# PROC051D_RST_LEDs.net
KiCad netlist of a schematic drawn in Altium Designer
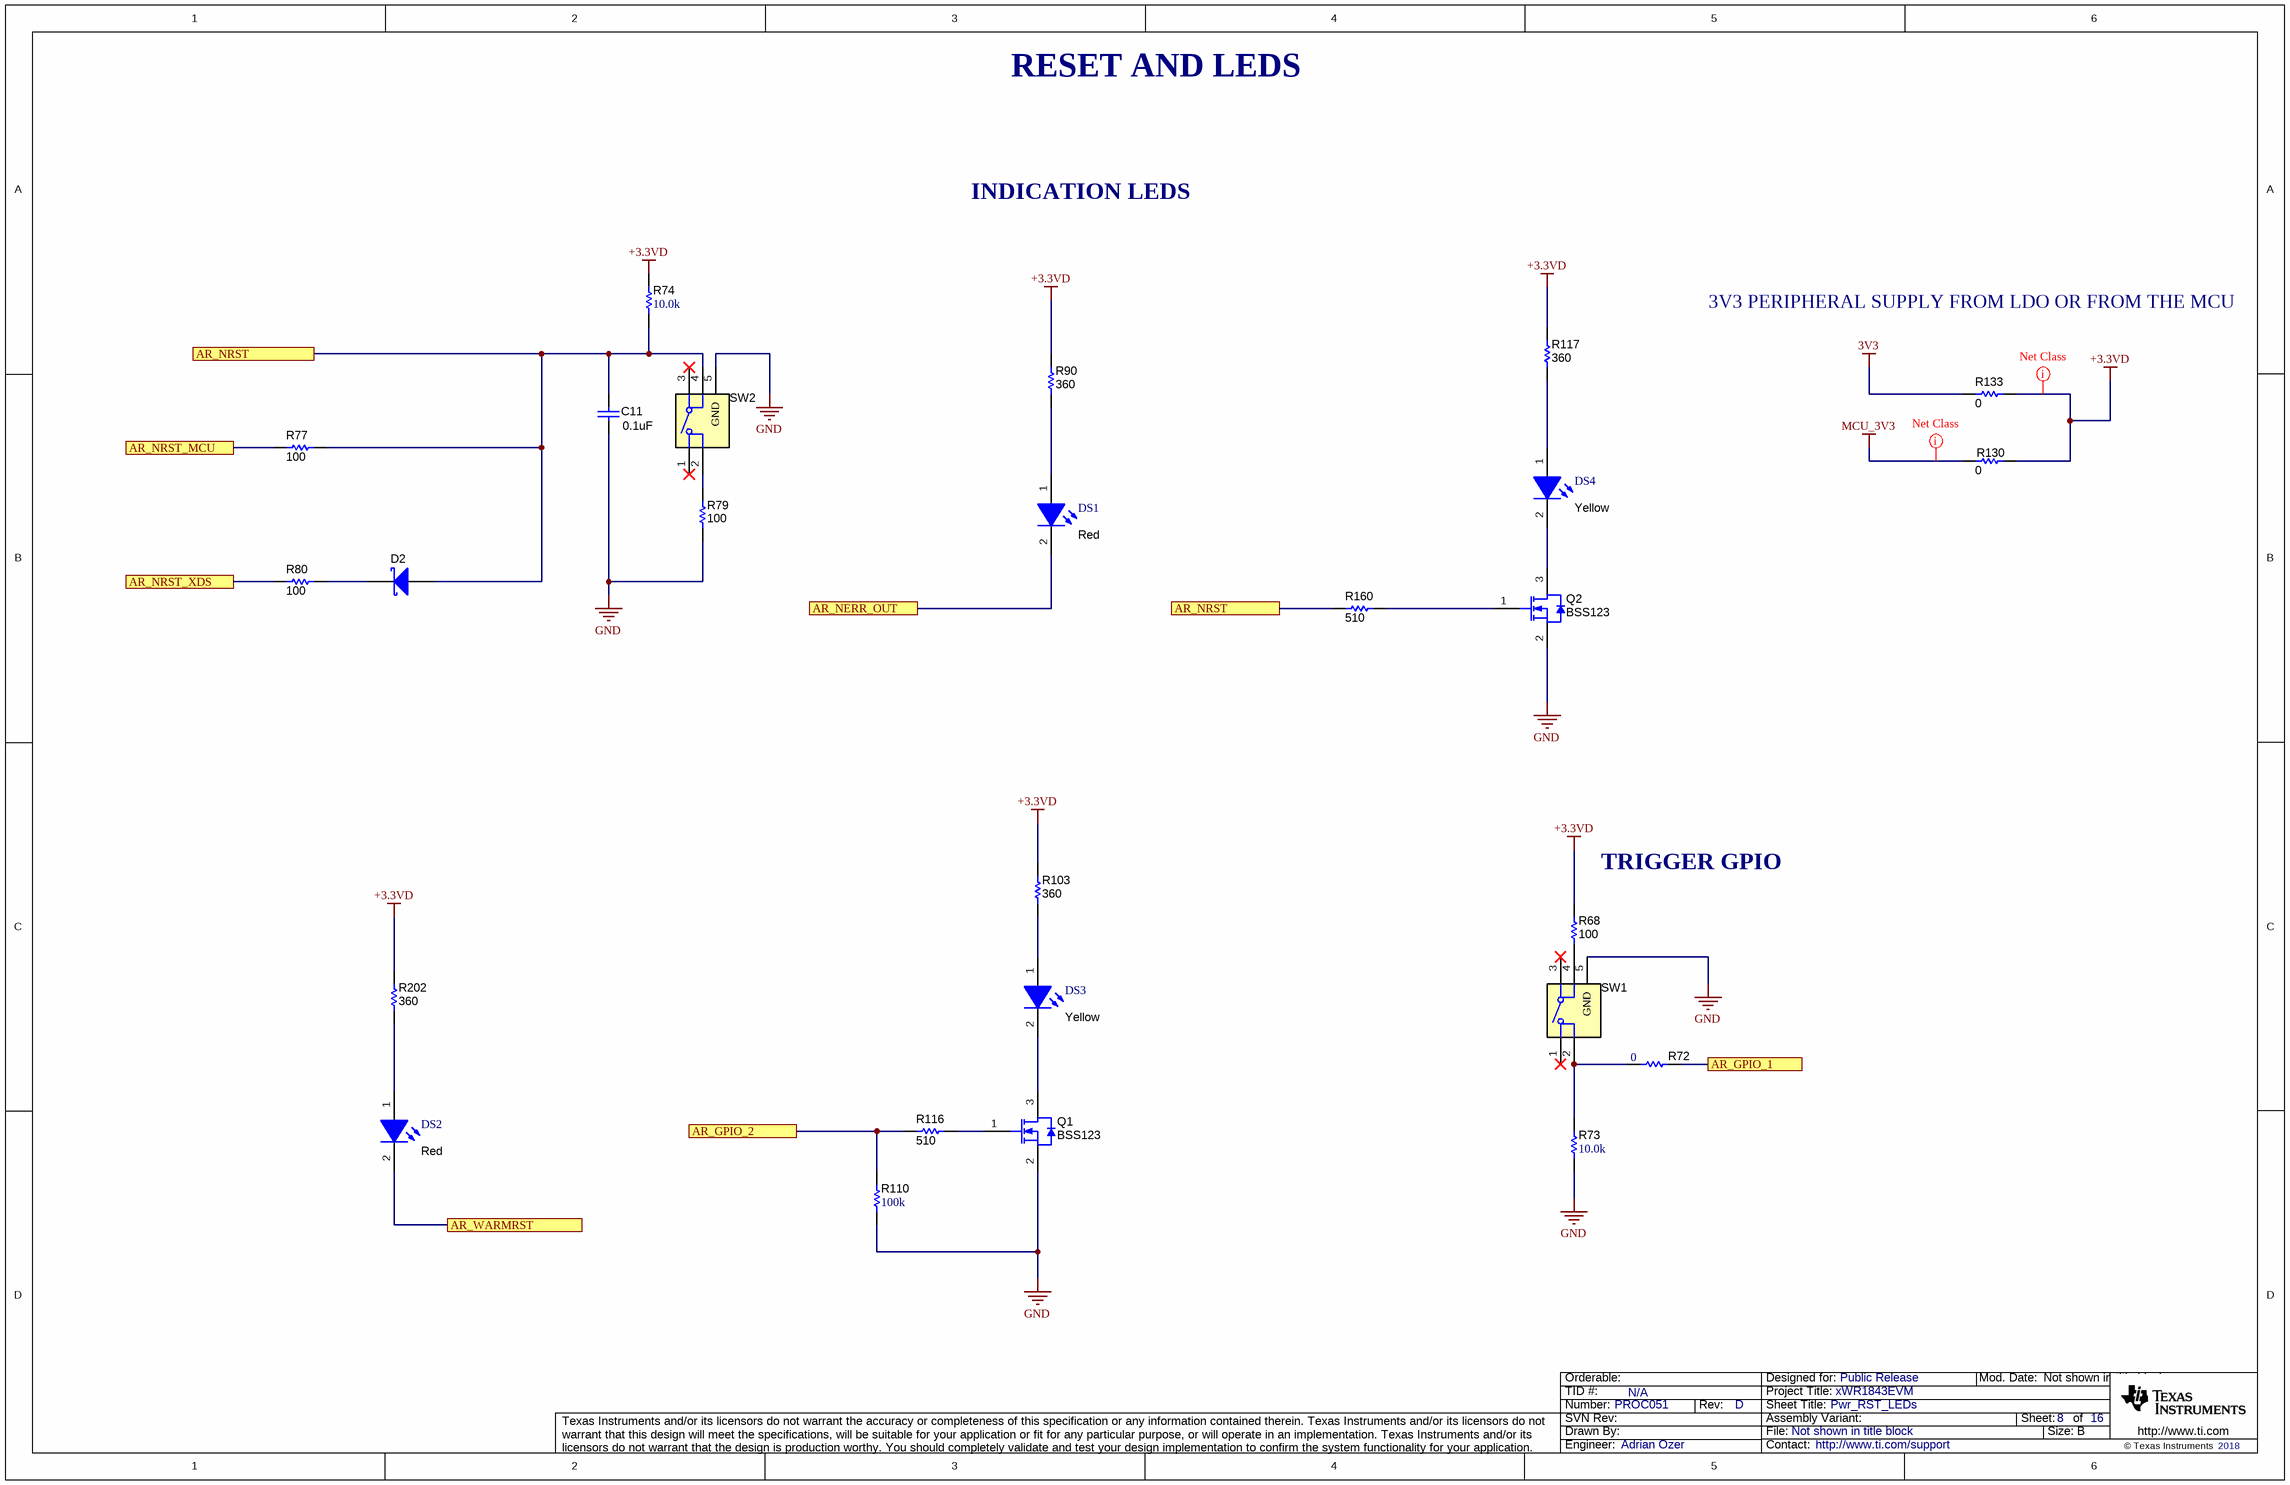
[diagram p0: PROC051D_RST_LEDs.SchDoc]

(export (version "E")
  (design (tool "Eeschema 10.0.6"))
  (components
    (comp (ref "C11")
      (value "GCM155R71C104KA55D")
      (footprint "0402L")
      (description "CAP, CERM, 0.1 uF, 16 V, +/- 10%, X7R, 0402")
      (fields
        (field (name "MANUFACTURER") "MuRata")
        (field (name "VALUEDISPLAYED") "0.1uF")
        (field (name "PUBLISHER") "Texas Instruments")
      )
      (libsource (lib "Altium Vault - TI") (part "Capacitor"))
    )
    (comp (ref "D2")
      (value "SMS3923-040LF")
      (footprint "SOD-882")
      (description "Diode, Schottky,  V, 0.01 A, SOD-882")
      (fields (field (name "MANUFACTURER") "Skyworks Solutions"))
      (libsource (lib "Altium Vault - TI") (part "DIODE_SCHOTTKY"))
    )
    (comp (ref "DS1")
      (value "Red")
      (footprint "LS L29K_Red")
      (description "LED, Red, SMD")
      (fields (field (name "MANUFACTURER") "OSRAM") (field (name "PARTNUMBER") "LS L29K-G1J2-1-Z"))
      (libsource (lib "Altium Vault - TI") (part "LED"))
    )
    (comp (ref "DS2")
      (value "Red")
      (footprint "LS L29K_Red")
      (description "LED, Red, SMD")
      (fields (field (name "MANUFACTURER") "OSRAM") (field (name "PARTNUMBER") "LS L29K-G1J2-1-Z"))
      (libsource (lib "Altium Vault - TI") (part "LED"))
    )
    (comp (ref "DS3")
      (value "Yellow")
      (footprint "SML-E1_Yellow")
      (description "LED, Yellow, SMD")
      (fields (field (name "MANUFACTURER") "Rohm") (field (name "PARTNUMBER") "SML-E12Y8WT86"))
      (libsource (lib "Altium Vault - TI") (part "LED"))
    )
    (comp (ref "DS4")
      (value "Yellow")
      (footprint "SML-E1_Yellow")
      (description "LED, Yellow, SMD")
      (fields (field (name "MANUFACTURER") "Rohm") (field (name "PARTNUMBER") "SML-E12Y8WT86"))
      (libsource (lib "Altium Vault - TI") (part "LED"))
    )
    (comp (ref "Q1")
      (value "BSS123")
      (footprint "SOT-23")
      (description "MOSFET, N-CH, 100 V, 0.17 A, SOT-23")
      (fields
        (field (name "MANUFACTURER") "Fairchild Semiconductor")
        (field (name "PUBLISHER") "Texas Instruments")
      )
      (libsource (lib "Altium Vault - TI") (part "MOSFET_N_D3G1S2"))
    )
    (comp (ref "Q2")
      (value "BSS123")
      (footprint "SOT-23")
      (description "MOSFET, N-CH, 100 V, 0.17 A, SOT-23")
      (fields
        (field (name "MANUFACTURER") "Fairchild Semiconductor")
        (field (name "PUBLISHER") "Texas Instruments")
      )
      (libsource (lib "Altium Vault - TI") (part "MOSFET_N_D3G1S2"))
    )
    (comp (ref "R68")
      (value "ERJ-2GEJ101X")
      (footprint "0402L")
      (description "RES, 100, 5%, 0.1 W, AEC-Q200 Grade 0, 0402")
      (fields
        (field (name "MANUFACTURER") "Panasonic")
        (field (name "VALUEDISPLAYED") "100")
        (field (name "PUBLISHER") "Texas Instruments")
      )
      (libsource (lib "Altium Vault - TI") (part "Resistor"))
    )
    (comp (ref "R72")
      (value "CRCW02010000Z0ED")
      (footprint "0201_Silk")
      (description "RES, 0, 5%, 0.05 W, 0201")
      (fields (field (name "MANUFACTURER") "Vishay-Dale") (field (name "VALUEDISPLAYED") "0"))
      (libsource (lib "Altium Vault - TI") (part "Resistor"))
    )
    (comp (ref "R73")
      (value "CRCW040210K0FKED")
      (footprint "0402L")
      (description "RES, 10.0 k, 1%, 0.063 W, AEC-Q200 Grade 0, 0402")
      (fields (field (name "MANUFACTURER") "Vishay-Dale") (field (name "VALUEDISPLAYED") "10.0k"))
      (libsource (lib "Altium Vault - TI") (part "Resistor"))
    )
    (comp (ref "R74")
      (value "CRCW040210K0FKED")
      (footprint "0402L")
      (description "RES, 10.0 k, 1%, 0.063 W, AEC-Q200 Grade 0, 0402")
      (fields (field (name "MANUFACTURER") "Vishay-Dale") (field (name "VALUEDISPLAYED") "10.0k"))
      (libsource (lib "Altium Vault - TI") (part "Resistor"))
    )
    (comp (ref "R77")
      (value "ERJ-2GEJ101X")
      (footprint "0402L")
      (description "RES, 100, 5%, 0.1 W, AEC-Q200 Grade 0, 0402")
      (fields
        (field (name "MANUFACTURER") "Panasonic")
        (field (name "VALUEDISPLAYED") "100")
        (field (name "PUBLISHER") "Texas Instruments")
      )
      (libsource (lib "Altium Vault - TI") (part "Resistor"))
    )
    (comp (ref "R79")
      (value "ERJ-2GEJ101X")
      (footprint "0402L")
      (description "RES, 100, 5%, 0.1 W, AEC-Q200 Grade 0, 0402")
      (fields
        (field (name "MANUFACTURER") "Panasonic")
        (field (name "VALUEDISPLAYED") "100")
        (field (name "PUBLISHER") "Texas Instruments")
      )
      (libsource (lib "Altium Vault - TI") (part "Resistor"))
    )
    (comp (ref "R80")
      (value "ERJ-2GEJ101X")
      (footprint "0402L")
      (description "RES, 100, 5%, 0.1 W, AEC-Q200 Grade 0, 0402")
      (fields
        (field (name "MANUFACTURER") "Panasonic")
        (field (name "VALUEDISPLAYED") "100")
        (field (name "PUBLISHER") "Texas Instruments")
      )
      (libsource (lib "Altium Vault - TI") (part "Resistor"))
    )
    (comp (ref "R90")
      (value "ERJ-2GEJ361X")
      (footprint "0402L")
      (description "RES, 360, 5%, 0.1 W, AEC-Q200 Grade 0, 0402")
      (fields (field (name "MANUFACTURER") "Panasonic") (field (name "VALUEDISPLAYED") "360"))
      (libsource (lib "Altium Vault - TI") (part "Resistor"))
    )
    (comp (ref "R103")
      (value "ERJ-2GEJ361X")
      (footprint "0402L")
      (description "RES, 360, 5%, 0.1 W, AEC-Q200 Grade 0, 0402")
      (fields (field (name "MANUFACTURER") "Panasonic") (field (name "VALUEDISPLAYED") "360"))
      (libsource (lib "Altium Vault - TI") (part "Resistor"))
    )
    (comp (ref "R110")
      (value "CRCW0402100KFKED")
      (footprint "0402L")
      (description "RES, 100 k, 1%, 0.063 W, AEC-Q200 Grade 0, 0402")
      (fields (field (name "MANUFACTURER") "Vishay-Dale") (field (name "VALUEDISPLAYED") "100k"))
      (libsource (lib "Altium Vault - TI") (part "Resistor"))
    )
    (comp (ref "R116")
      (value "ERJ-2GEJ511X")
      (footprint "0402L")
      (description "RES, 510, 5%, 0.1 W, AEC-Q200 Grade 0, 0402")
      (fields (field (name "MANUFACTURER") "Panasonic") (field (name "VALUEDISPLAYED") "510"))
      (libsource (lib "Altium Vault - TI") (part "Resistor"))
    )
    (comp (ref "R117")
      (value "ERJ-2GEJ361X")
      (footprint "0402L")
      (description "RES, 360, 5%, 0.1 W, AEC-Q200 Grade 0, 0402")
      (fields (field (name "MANUFACTURER") "Panasonic") (field (name "VALUEDISPLAYED") "360"))
      (libsource (lib "Altium Vault - TI") (part "Resistor"))
    )
    (comp (ref "R130")
      (value "MCT06030Z0000ZP500")
      (footprint "0603")
      (description "RES, 0, 5%, 0.125 W, 0603")
      (fields
        (field (name "MANUFACTURER") "Vishay/Beyschlag")
        (field (name "VALUEDISPLAYED") "0")
        (field (name "PUBLISHER") "Texas Instruments")
      )
      (libsource (lib "Altium Vault - TI") (part "CMP-0025884-3"))
    )
    (comp (ref "R133")
      (value "MCT06030Z0000ZP500")
      (footprint "0603")
      (description "RES, 0, 5%, 0.125 W, 0603")
      (fields
        (field (name "MANUFACTURER") "Vishay/Beyschlag")
        (field (name "VALUEDISPLAYED") "0")
        (field (name "PUBLISHER") "Texas Instruments")
      )
      (libsource (lib "Altium Vault - TI") (part "Resistor"))
    )
    (comp (ref "R160")
      (value "ERJ-2GEJ511X")
      (footprint "0402L")
      (description "RES, 510, 5%, 0.1 W, AEC-Q200 Grade 0, 0402")
      (fields (field (name "MANUFACTURER") "Panasonic") (field (name "VALUEDISPLAYED") "510"))
      (libsource (lib "Altium Vault - TI") (part "Resistor"))
    )
    (comp (ref "R202")
      (value "ERJ-2GEJ361X")
      (footprint "0402L")
      (description "RES, 360, 5%, 0.1 W, AEC-Q200 Grade 0, 0402")
      (fields (field (name "MANUFACTURER") "Panasonic") (field (name "VALUEDISPLAYED") "360"))
      (libsource (lib "Altium Vault - TI") (part "Resistor"))
    )
    (comp (ref "SW1")
      (value "KMR243GLFG")
      (footprint "SW_KMR243GLFG")
      (description "Switch, SPST-NO, Off-Mom, 0.01 A, 32 VDC, SMD")
      (fields (field (name "MANUFACTURER") "C&K Components") (field (name "PUBLISHER") "Texas Instruments"))
      (libsource (lib "Altium Vault - TI") (part "CMP-0002325-1"))
    )
    (comp (ref "SW2")
      (value "KMR243GLFG")
      (footprint "SW_KMR243GLFG")
      (description "Switch, SPST-NO, Off-Mom, 0.01 A, 32 VDC, SMD")
      (fields (field (name "MANUFACTURER") "C&K Components") (field (name "PUBLISHER") "Texas Instruments"))
      (libsource (lib "Altium Vault - TI") (part "CMP-0002325-1"))
    )
  )
  (nets
    (net (code "1") (name "+3.3VD") (class "Default")
      (node (ref "R103") (pin "2") (pinfunction "2_2") (pintype "passive"))
      (node (ref "R117") (pin "2") (pinfunction "2_2") (pintype "passive"))
      (node (ref "R130") (pin "2") (pinfunction "2_2") (pintype "passive"))
      (node (ref "R133") (pin "2") (pinfunction "2_2") (pintype "passive"))
      (node (ref "R202") (pin "2") (pinfunction "2_2") (pintype "passive"))
      (node (ref "R68") (pin "2") (pinfunction "2_2") (pintype "passive"))
      (node (ref "R74") (pin "2") (pinfunction "2_2") (pintype "passive"))
      (node (ref "R90") (pin "2") (pinfunction "2_2") (pintype "passive"))
    )
    (net (code "2") (name "/AR_GPIO_1") (class "Default")
      (node (ref "R72") (pin "2") (pinfunction "2_2") (pintype "passive"))
    )
    (net (code "3") (name "/AR_GPIO_2") (class "Default")
      (node (ref "R110") (pin "2") (pinfunction "2_2") (pintype "passive"))
      (node (ref "R116") (pin "1") (pinfunction "1_1") (pintype "passive"))
    )
    (net (code "4") (name "/AR_NERR_OUT") (class "Default")
      (node (ref "DS1") (pin "2") (pinfunction "K_2") (pintype "passive"))
    )
    (net (code "5") (name "/AR_NRST") (class "Default")
      (node (ref "C11") (pin "2") (pinfunction "2_2") (pintype "passive"))
      (node (ref "D2") (pin "2") (pinfunction "A_2") (pintype "passive"))
      (node (ref "R160") (pin "1") (pinfunction "1_1") (pintype "passive"))
      (node (ref "R74") (pin "1") (pinfunction "1_1") (pintype "passive"))
      (node (ref "R77") (pin "2") (pinfunction "2_2") (pintype "passive"))
      (node (ref "SW2") (pin "4") (pinfunction "4_4") (pintype "passive"))
    )
    (net (code "6") (name "/AR_NRST_MCU") (class "Default")
      (node (ref "R77") (pin "1") (pinfunction "1_1") (pintype "passive"))
    )
    (net (code "7") (name "/AR_NRST_XDS") (class "Default")
      (node (ref "R80") (pin "1") (pinfunction "1_1") (pintype "passive"))
    )
    (net (code "8") (name "/AR_WARMRST") (class "Default")
      (node (ref "DS2") (pin "2") (pinfunction "K_2") (pintype "passive"))
    )
    (net (code "9") (name "3V3") (class "Default")
      (node (ref "R133") (pin "1") (pinfunction "1_1") (pintype "passive"))
    )
    (net (code "10") (name "GND") (class "Default")
      (node (ref "C11") (pin "1") (pinfunction "1_1") (pintype "passive"))
      (node (ref "Q1") (pin "2") (pinfunction "S_2") (pintype "passive"))
      (node (ref "Q2") (pin "2") (pinfunction "S_2") (pintype "passive"))
      (node (ref "R110") (pin "1") (pinfunction "1_1") (pintype "passive"))
      (node (ref "R73") (pin "1") (pinfunction "1_1") (pintype "passive"))
      (node (ref "R79") (pin "1") (pinfunction "1_1") (pintype "passive"))
      (node (ref "SW1") (pin "5") (pinfunction "GND_5") (pintype "passive"))
      (node (ref "SW2") (pin "5") (pinfunction "GND_5") (pintype "passive"))
    )
    (net (code "11") (name "MCU_3V3") (class "Default")
      (node (ref "R130") (pin "1") (pinfunction "1_1") (pintype "passive"))
    )
    (net (code "12") (name "Net-(D2-K)") (class "Default")
      (node (ref "D2") (pin "1") (pinfunction "K_1") (pintype "passive"))
      (node (ref "R80") (pin "2") (pinfunction "2_2") (pintype "passive"))
    )
    (net (code "13") (name "Net-(DS1-A)") (class "Default")
      (node (ref "DS1") (pin "1") (pinfunction "A_1") (pintype "passive"))
      (node (ref "R90") (pin "1") (pinfunction "1_1") (pintype "passive"))
    )
    (net (code "14") (name "Net-(DS2-A)") (class "Default")
      (node (ref "DS2") (pin "1") (pinfunction "A_1") (pintype "passive"))
      (node (ref "R202") (pin "1") (pinfunction "1_1") (pintype "passive"))
    )
    (net (code "15") (name "Net-(DS3-A)") (class "Default")
      (node (ref "DS3") (pin "1") (pinfunction "A_1") (pintype "passive"))
      (node (ref "R103") (pin "1") (pinfunction "1_1") (pintype "passive"))
    )
    (net (code "16") (name "Net-(DS3-K)") (class "Default")
      (node (ref "DS3") (pin "2") (pinfunction "K_2") (pintype "passive"))
      (node (ref "Q1") (pin "3") (pinfunction "D_3") (pintype "passive"))
    )
    (net (code "17") (name "Net-(DS4-A)") (class "Default")
      (node (ref "DS4") (pin "1") (pinfunction "A_1") (pintype "passive"))
      (node (ref "R117") (pin "1") (pinfunction "1_1") (pintype "passive"))
    )
    (net (code "18") (name "Net-(DS4-K)") (class "Default")
      (node (ref "DS4") (pin "2") (pinfunction "K_2") (pintype "passive"))
      (node (ref "Q2") (pin "3") (pinfunction "D_3") (pintype "passive"))
    )
    (net (code "19") (name "Net-(Q1-G)") (class "Default")
      (node (ref "Q1") (pin "1") (pinfunction "G_1") (pintype "passive"))
      (node (ref "R116") (pin "2") (pinfunction "2_2") (pintype "passive"))
    )
    (net (code "20") (name "Net-(Q2-G)") (class "Default")
      (node (ref "Q2") (pin "1") (pinfunction "G_1") (pintype "passive"))
      (node (ref "R160") (pin "2") (pinfunction "2_2") (pintype "passive"))
    )
    (net (code "21") (name "Net-(R68-Pad1)") (class "Default")
      (node (ref "R68") (pin "1") (pinfunction "1_1") (pintype "passive"))
      (node (ref "SW1") (pin "4") (pinfunction "4_4") (pintype "passive"))
    )
    (net (code "22") (name "Net-(R72-Pad1)") (class "Default")
      (node (ref "R72") (pin "1") (pinfunction "1_1") (pintype "passive"))
      (node (ref "R73") (pin "2") (pinfunction "2_2") (pintype "passive"))
      (node (ref "SW1") (pin "2") (pinfunction "2_2") (pintype "passive"))
    )
    (net (code "23") (name "Net-(R79-Pad2)") (class "Default")
      (node (ref "R79") (pin "2") (pinfunction "2_2") (pintype "passive"))
      (node (ref "SW2") (pin "2") (pinfunction "2_2") (pintype "passive"))
    )
    (net (code "24") (name "unconnected-(SW1-Pad1)") (class "Default")
      (node (ref "SW1") (pin "1") (pinfunction "1_1") (pintype "passive+no_connect"))
    )
    (net (code "25") (name "unconnected-(SW1-Pad3)") (class "Default")
      (node (ref "SW1") (pin "3") (pinfunction "3_3") (pintype "passive+no_connect"))
    )
    (net (code "26") (name "unconnected-(SW2-Pad1)") (class "Default")
      (node (ref "SW2") (pin "1") (pinfunction "1_1") (pintype "passive+no_connect"))
    )
    (net (code "27") (name "unconnected-(SW2-Pad3)") (class "Default")
      (node (ref "SW2") (pin "3") (pinfunction "3_3") (pintype "passive+no_connect"))
    )
  )
)
